# schematic.net
KiCad netlist of a schematic drawn in EAGLE
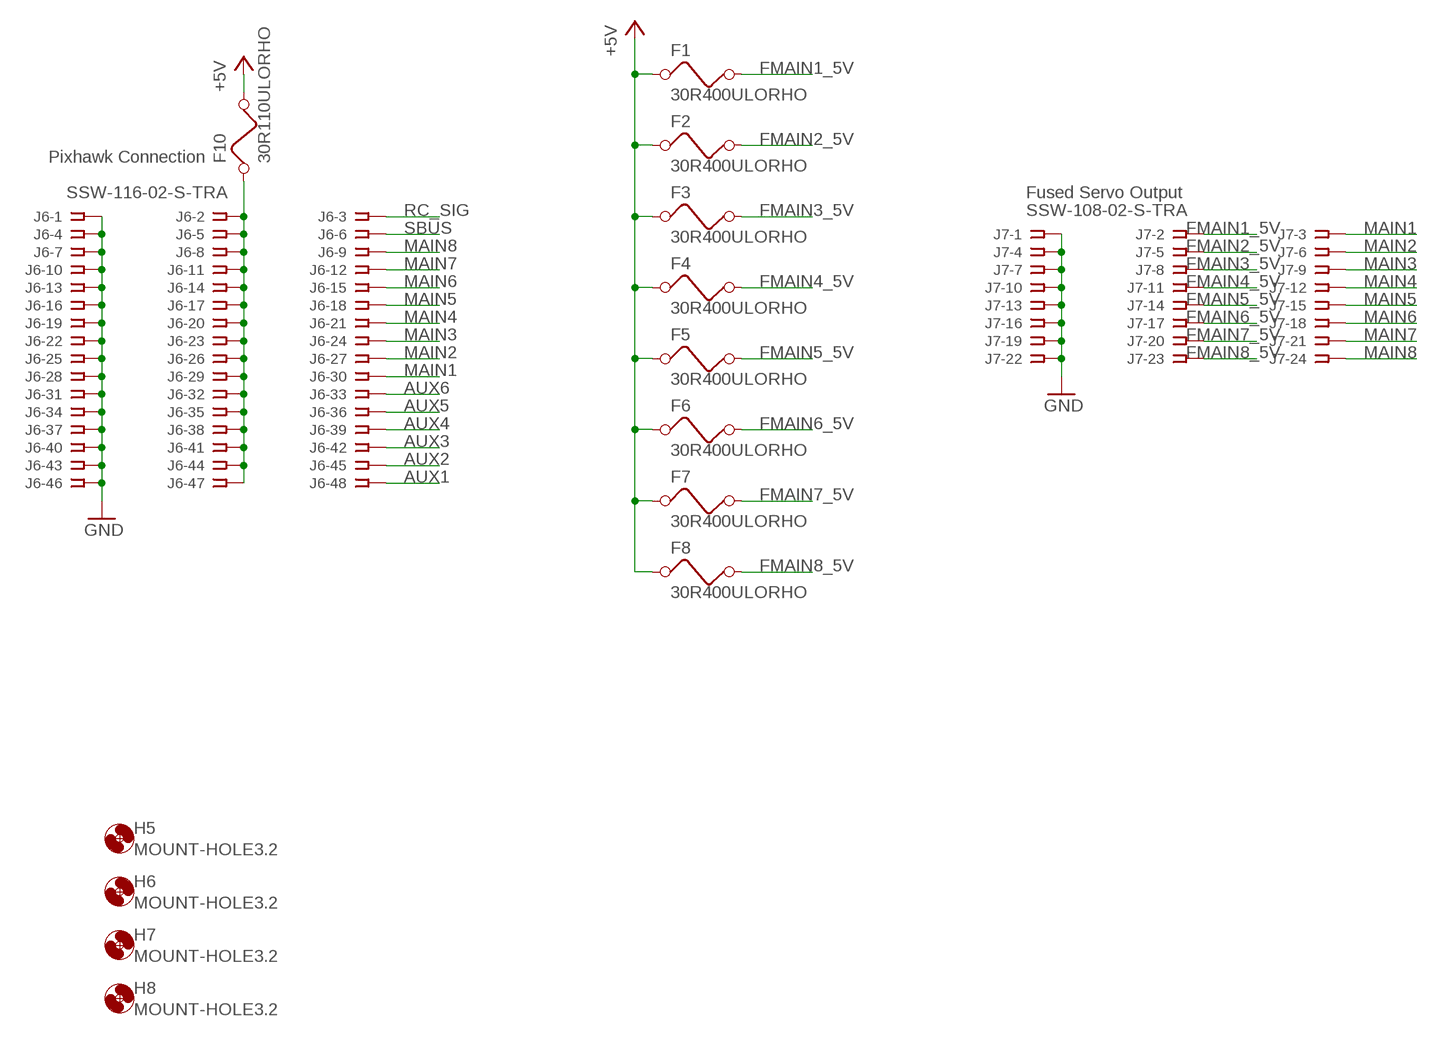
[diagram p0: schematic, sheet 1]
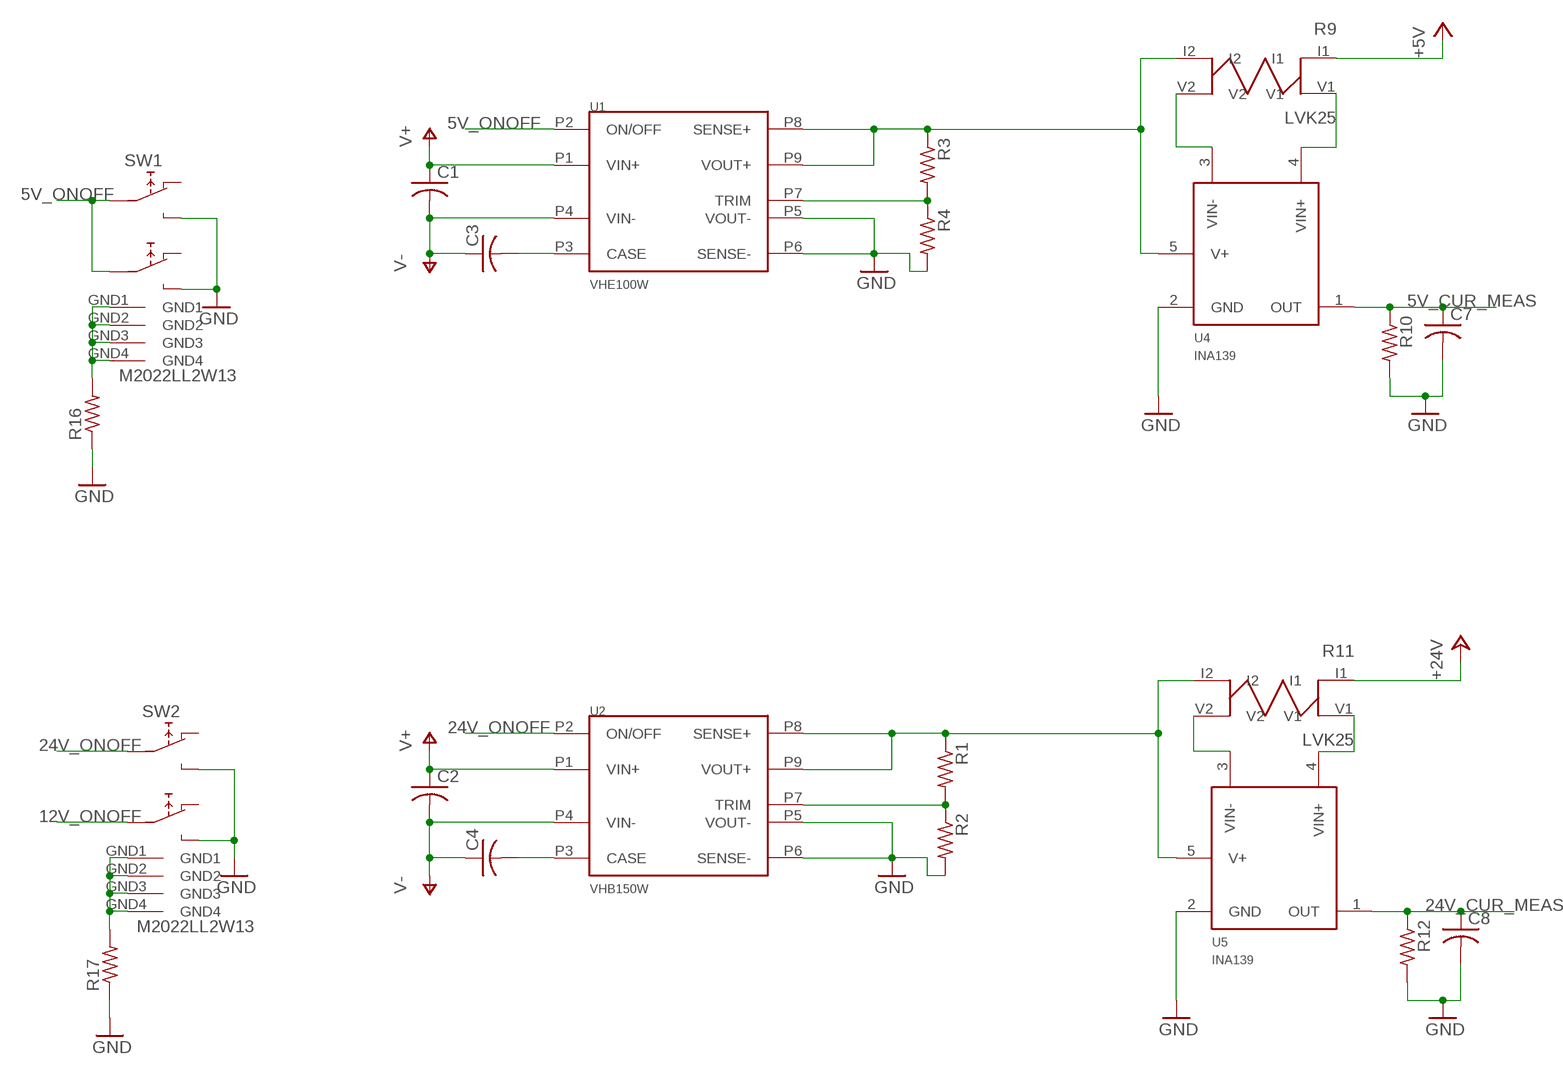
[diagram p1: schematic, sheet 2, part 1 of 2]
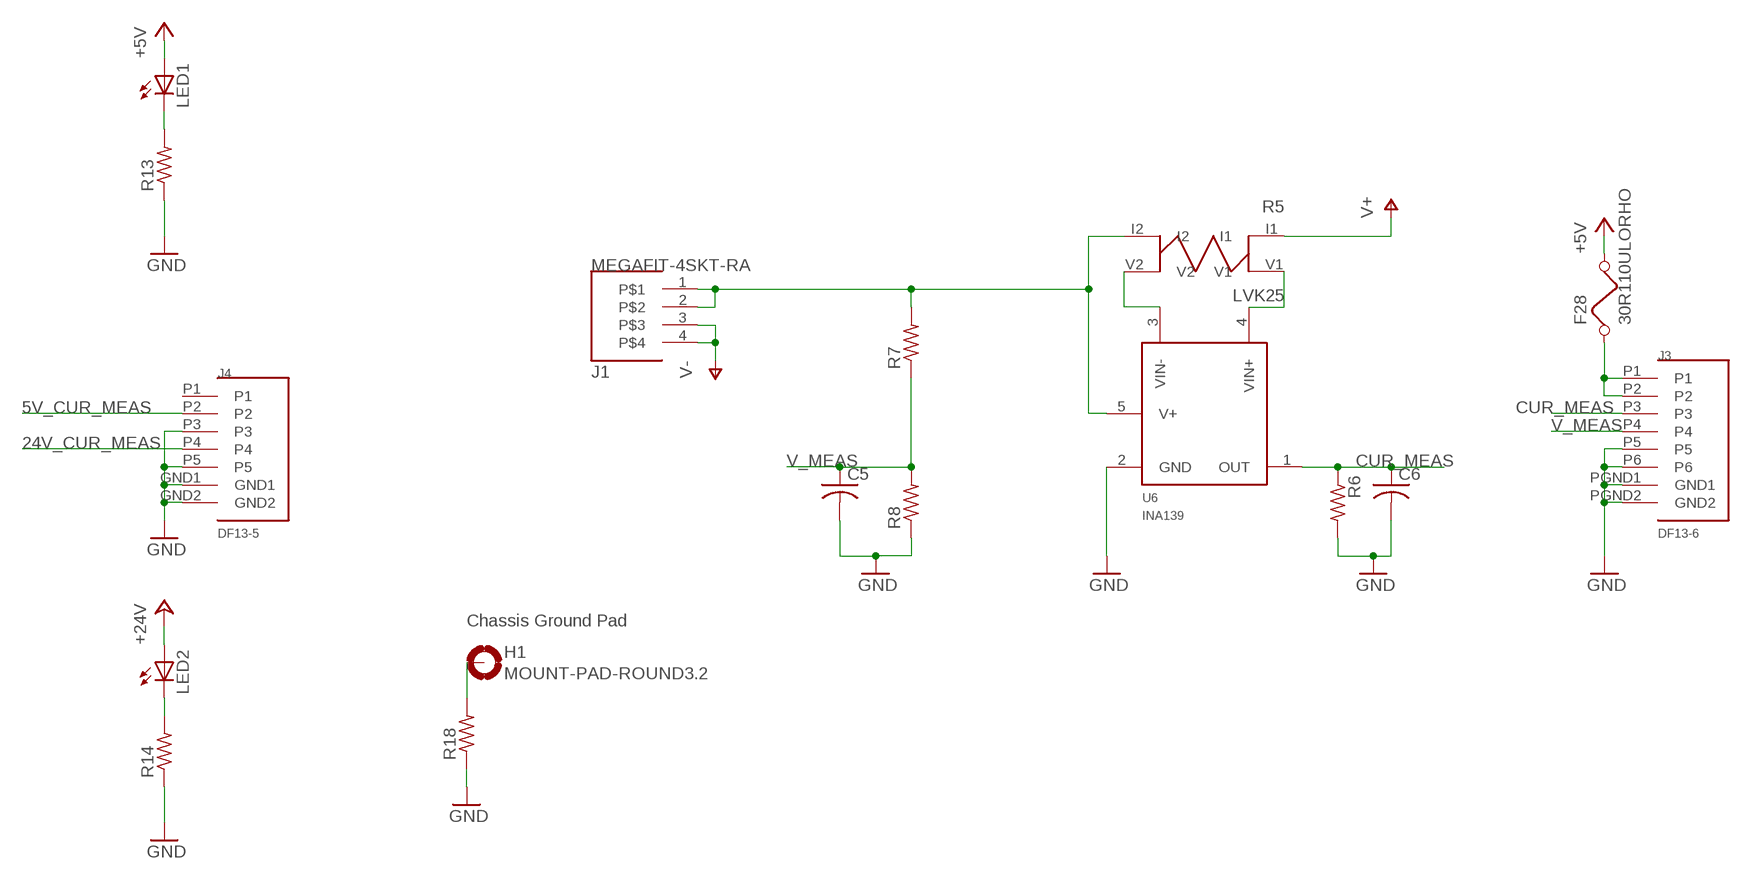
[diagram p2: schematic, sheet 2, part 2 of 2]
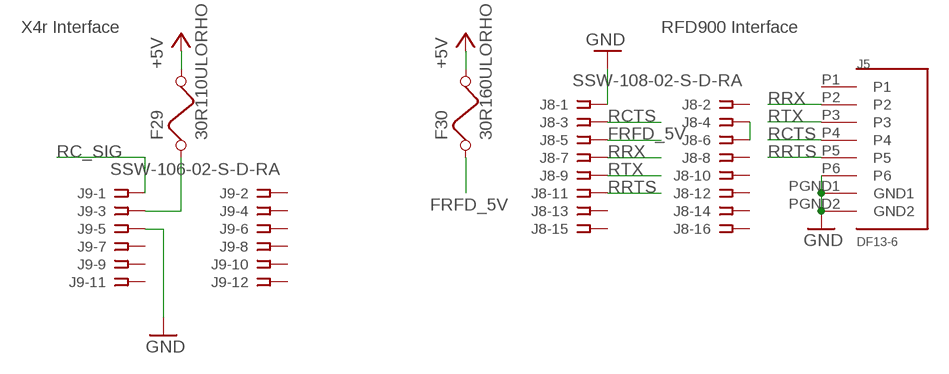
[diagram p3: schematic, sheet 3]
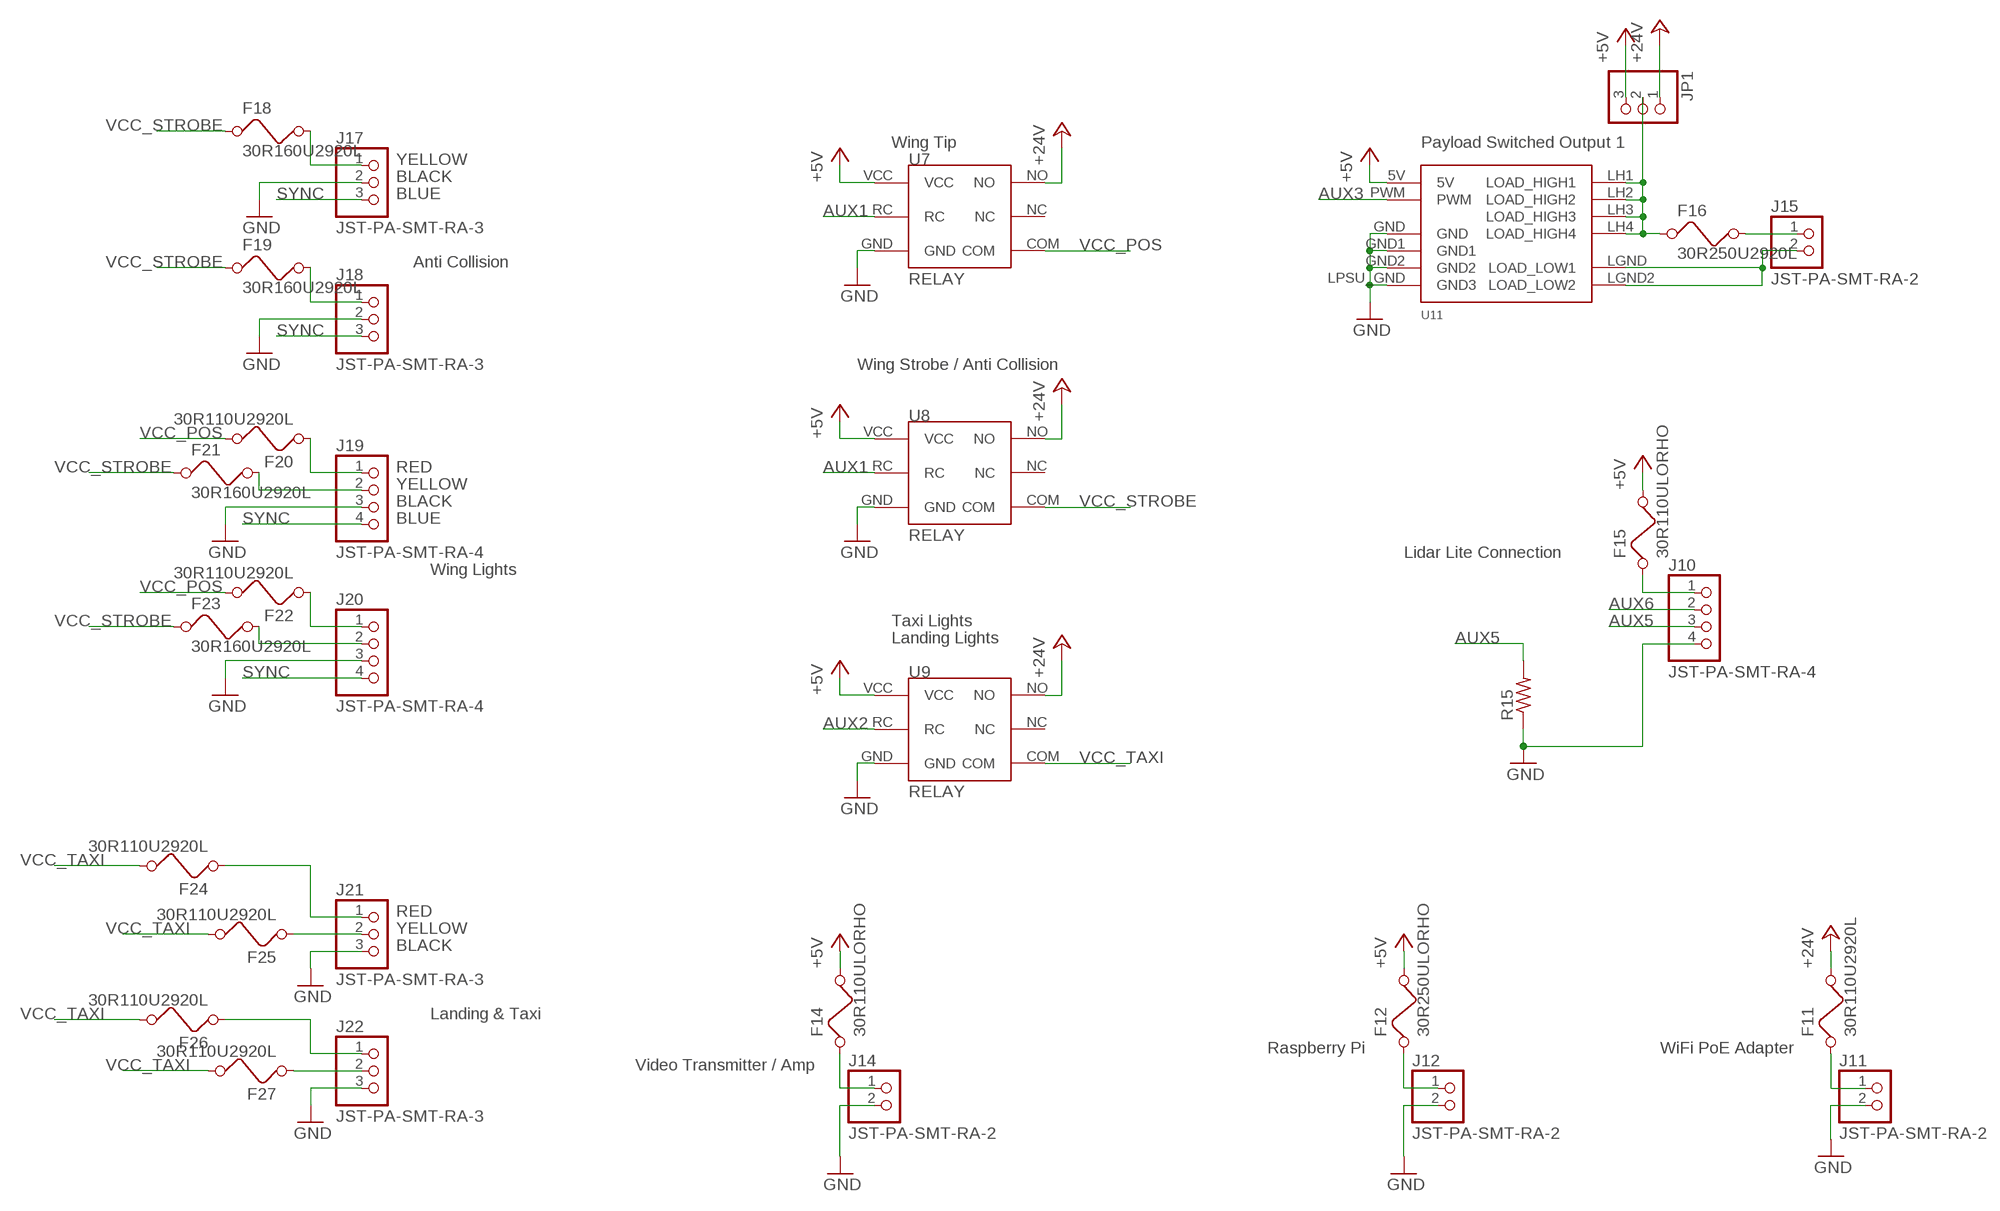
[diagram p4: schematic, sheet 4]

(export (version "E")
  (design (tool "Eeschema 10.0.6"))
  (components
    (comp (ref "F1")
      (value "30R400ULORHO")
      (footprint "eagle-import:1206")
      (libsource (lib "eagle-import") (part "30R400ULORHO"))
    )
    (comp (ref "F2")
      (value "30R400ULORHO")
      (footprint "eagle-import:1206")
      (libsource (lib "eagle-import") (part "30R400ULORHO"))
    )
    (comp (ref "F3")
      (value "30R400ULORHO")
      (footprint "eagle-import:1206")
      (libsource (lib "eagle-import") (part "30R400ULORHO"))
    )
    (comp (ref "F4")
      (value "30R400ULORHO")
      (footprint "eagle-import:1206")
      (libsource (lib "eagle-import") (part "30R400ULORHO"))
    )
    (comp (ref "F5")
      (value "30R400ULORHO")
      (footprint "eagle-import:1206")
      (libsource (lib "eagle-import") (part "30R400ULORHO"))
    )
    (comp (ref "F6")
      (value "30R400ULORHO")
      (footprint "eagle-import:1206")
      (libsource (lib "eagle-import") (part "30R400ULORHO"))
    )
    (comp (ref "F7")
      (value "30R400ULORHO")
      (footprint "eagle-import:1206")
      (libsource (lib "eagle-import") (part "30R400ULORHO"))
    )
    (comp (ref "F8")
      (value "30R400ULORHO")
      (footprint "eagle-import:1206")
      (libsource (lib "eagle-import") (part "30R400ULORHO"))
    )
    (comp (ref "F10")
      (value "30R110ULORHO")
      (footprint "eagle-import:1206")
      (libsource (lib "eagle-import") (part "30R110ULORHO"))
    )
    (comp (ref "H5")
      (value "MOUNT-HOLE3.2")
      (footprint "eagle-import:3,2")
      (libsource (lib "eagle-import") (part "MOUNT-HOLE3.2"))
    )
    (comp (ref "H6")
      (value "MOUNT-HOLE3.2")
      (footprint "eagle-import:3,2")
      (libsource (lib "eagle-import") (part "MOUNT-HOLE3.2"))
    )
    (comp (ref "H7")
      (value "MOUNT-HOLE3.2")
      (footprint "eagle-import:3,2")
      (libsource (lib "eagle-import") (part "MOUNT-HOLE3.2"))
    )
    (comp (ref "H8")
      (value "MOUNT-HOLE3.2")
      (footprint "eagle-import:3,2")
      (libsource (lib "eagle-import") (part "MOUNT-HOLE3.2"))
    )
    (comp (ref "J6")
      (value "SSW-116-02-S-TRA")
      (footprint "eagle-import:SSW-116-02-S-T-RA")
      (fields (field (name "MPN") "SSW-116-02-S-T-RA"))
      (libsource (lib "eagle-import") (part "SSW-116-02-S-TRA"))
    )
    (comp (ref "J7")
      (value "SSW-108-02-S-TRA")
      (footprint "eagle-import:SSW-108-02-S-T-RA")
      (fields (field (name "MPN") "SSW-108-02-S-T-RA"))
      (libsource (lib "eagle-import") (part "SSW-108-02-S-TRA"))
    )
    (comp (ref "C1")
      (value "C-USC1210")
      (footprint "eagle-import:C1210")
      (libsource (lib "eagle-import") (part "C-USC1210"))
    )
    (comp (ref "C2")
      (value "C-USC1210")
      (footprint "eagle-import:C1210")
      (libsource (lib "eagle-import") (part "C-USC1210"))
    )
    (comp (ref "C3")
      (value "C-USC1210")
      (footprint "eagle-import:C1210")
      (libsource (lib "eagle-import") (part "C-USC1210"))
    )
    (comp (ref "C4")
      (value "C-USC1210")
      (footprint "eagle-import:C1210")
      (libsource (lib "eagle-import") (part "C-USC1210"))
    )
    (comp (ref "C5")
      (value "C-USC0805")
      (footprint "eagle-import:C0805")
      (libsource (lib "eagle-import") (part "C-USC0805"))
    )
    (comp (ref "C6")
      (value "C-USC0805")
      (footprint "eagle-import:C0805")
      (libsource (lib "eagle-import") (part "C-USC0805"))
    )
    (comp (ref "C7")
      (value "C-USC0805")
      (footprint "eagle-import:C0805")
      (libsource (lib "eagle-import") (part "C-USC0805"))
    )
    (comp (ref "C8")
      (value "C-USC0805")
      (footprint "eagle-import:C0805")
      (libsource (lib "eagle-import") (part "C-USC0805"))
    )
    (comp (ref "F28")
      (value "30R110ULORHO")
      (footprint "eagle-import:1206")
      (libsource (lib "eagle-import") (part "30R110ULORHO"))
    )
    (comp (ref "H1")
      (value "MOUNT-PAD-ROUND3.2")
      (footprint "eagle-import:3,2-PAD")
      (libsource (lib "eagle-import") (part "MOUNT-PAD-ROUND3.2"))
    )
    (comp (ref "J1")
      (value "MEGAFIT-4SKT-RA")
      (footprint "eagle-import:MEGAFIT-4SKT-RA")
      (libsource (lib "eagle-import") (part "MEGAFIT-4SKT-RA"))
    )
    (comp (ref "J3")
      (value "DF13-6")
      (footprint "eagle-import:DF13-6")
      (libsource (lib "eagle-import") (part "DF13-6"))
    )
    (comp (ref "J4")
      (value "DF13-5")
      (footprint "eagle-import:DF13-5")
      (libsource (lib "eagle-import") (part "DF13-5"))
    )
    (comp (ref "LED1")
      (value "LEDCHIPLED_0805")
      (footprint "eagle-import:CHIPLED_0805")
      (libsource (lib "eagle-import") (part "LEDCHIPLED_0805"))
    )
    (comp (ref "LED2")
      (value "LEDCHIPLED_0805")
      (footprint "eagle-import:CHIPLED_0805")
      (libsource (lib "eagle-import") (part "LEDCHIPLED_0805"))
    )
    (comp (ref "R1")
      (value "R-US_M0805")
      (footprint "eagle-import:M0805")
      (libsource (lib "eagle-import") (part "R-US_M0805"))
    )
    (comp (ref "R2")
      (value "R-US_M0805")
      (footprint "eagle-import:M0805")
      (libsource (lib "eagle-import") (part "R-US_M0805"))
    )
    (comp (ref "R3")
      (value "R-US_M0805")
      (footprint "eagle-import:M0805")
      (libsource (lib "eagle-import") (part "R-US_M0805"))
    )
    (comp (ref "R4")
      (value "R-US_M0805")
      (footprint "eagle-import:M0805")
      (libsource (lib "eagle-import") (part "R-US_M0805"))
    )
    (comp (ref "R5")
      (value "LVK25")
      (footprint "eagle-import:LVK25")
      (libsource (lib "eagle-import") (part "LVK25"))
    )
    (comp (ref "R6")
      (value "R-US_M0805")
      (footprint "eagle-import:M0805")
      (libsource (lib "eagle-import") (part "R-US_M0805"))
    )
    (comp (ref "R7")
      (value "R-US_M0805")
      (footprint "eagle-import:M0805")
      (libsource (lib "eagle-import") (part "R-US_M0805"))
    )
    (comp (ref "R8")
      (value "R-US_M0805")
      (footprint "eagle-import:M0805")
      (libsource (lib "eagle-import") (part "R-US_M0805"))
    )
    (comp (ref "R9")
      (value "LVK25")
      (footprint "eagle-import:LVK25")
      (libsource (lib "eagle-import") (part "LVK25"))
    )
    (comp (ref "R10")
      (value "R-US_M0805")
      (footprint "eagle-import:M0805")
      (libsource (lib "eagle-import") (part "R-US_M0805"))
    )
    (comp (ref "R11")
      (value "LVK25")
      (footprint "eagle-import:LVK25")
      (libsource (lib "eagle-import") (part "LVK25"))
    )
    (comp (ref "R12")
      (value "R-US_M0805")
      (footprint "eagle-import:M0805")
      (libsource (lib "eagle-import") (part "R-US_M0805"))
    )
    (comp (ref "R13")
      (value "R-US_M0805")
      (footprint "eagle-import:M0805")
      (libsource (lib "eagle-import") (part "R-US_M0805"))
    )
    (comp (ref "R14")
      (value "R-US_M0805")
      (footprint "eagle-import:M0805")
      (libsource (lib "eagle-import") (part "R-US_M0805"))
    )
    (comp (ref "R16")
      (value "R-US_M0805")
      (footprint "eagle-import:M0805")
      (libsource (lib "eagle-import") (part "R-US_M0805"))
    )
    (comp (ref "R17")
      (value "R-US_M0805")
      (footprint "eagle-import:M0805")
      (libsource (lib "eagle-import") (part "R-US_M0805"))
    )
    (comp (ref "R18")
      (value "R-US_M0805")
      (footprint "eagle-import:M0805")
      (libsource (lib "eagle-import") (part "R-US_M0805"))
    )
    (comp (ref "SW1")
      (value "M2022LL2W13")
      (footprint "eagle-import:M2022LL2W13")
      (libsource (lib "eagle-import") (part "M2022LL2W13"))
    )
    (comp (ref "SW2")
      (value "M2022LL2W13")
      (footprint "eagle-import:M2022LL2W13")
      (libsource (lib "eagle-import") (part "M2022LL2W13"))
    )
    (comp (ref "U1")
      (value "VHE100W")
      (footprint "eagle-import:VHE100W")
      (libsource (lib "eagle-import") (part "VHE100W"))
    )
    (comp (ref "U2")
      (value "VHB150W")
      (footprint "eagle-import:VHB150W")
      (libsource (lib "eagle-import") (part "VHB150W"))
    )
    (comp (ref "U4")
      (value "INA139")
      (footprint "eagle-import:SOT23-5")
      (libsource (lib "eagle-import") (part "INA139"))
    )
    (comp (ref "U5")
      (value "INA139")
      (footprint "eagle-import:SOT23-5")
      (libsource (lib "eagle-import") (part "INA139"))
    )
    (comp (ref "U6")
      (value "INA139")
      (footprint "eagle-import:SOT23-5")
      (libsource (lib "eagle-import") (part "INA139"))
    )
    (comp (ref "F11")
      (value "30R110U2920L")
      (footprint "eagle-import:2920L")
      (libsource (lib "eagle-import") (part "30R110U2920L"))
    )
    (comp (ref "F12")
      (value "30R250ULORHO")
      (footprint "eagle-import:1206")
      (libsource (lib "eagle-import") (part "30R250ULORHO"))
    )
    (comp (ref "F14")
      (value "30R110ULORHO")
      (footprint "eagle-import:1206")
      (libsource (lib "eagle-import") (part "30R110ULORHO"))
    )
    (comp (ref "F15")
      (value "30R110ULORHO")
      (footprint "eagle-import:1206")
      (libsource (lib "eagle-import") (part "30R110ULORHO"))
    )
    (comp (ref "F16")
      (value "30R250U2920L")
      (footprint "eagle-import:2920L")
      (libsource (lib "eagle-import") (part "30R250U2920L"))
    )
    (comp (ref "F18")
      (value "30R160U2920L")
      (footprint "eagle-import:2920L")
      (libsource (lib "eagle-import") (part "30R160U2920L"))
    )
    (comp (ref "F19")
      (value "30R160U2920L")
      (footprint "eagle-import:2920L")
      (libsource (lib "eagle-import") (part "30R160U2920L"))
    )
    (comp (ref "F20")
      (value "30R110U2920L")
      (footprint "eagle-import:2920L")
      (libsource (lib "eagle-import") (part "30R110U2920L"))
    )
    (comp (ref "F21")
      (value "30R160U2920L")
      (footprint "eagle-import:2920L")
      (libsource (lib "eagle-import") (part "30R160U2920L"))
    )
    (comp (ref "F22")
      (value "30R110U2920L")
      (footprint "eagle-import:2920L")
      (libsource (lib "eagle-import") (part "30R110U2920L"))
    )
    (comp (ref "F23")
      (value "30R160U2920L")
      (footprint "eagle-import:2920L")
      (libsource (lib "eagle-import") (part "30R160U2920L"))
    )
    (comp (ref "F24")
      (value "30R110U2920L")
      (footprint "eagle-import:2920L")
      (libsource (lib "eagle-import") (part "30R110U2920L"))
    )
    (comp (ref "F25")
      (value "30R110U2920L")
      (footprint "eagle-import:2920L")
      (libsource (lib "eagle-import") (part "30R110U2920L"))
    )
    (comp (ref "F26")
      (value "30R110U2920L")
      (footprint "eagle-import:2920L")
      (libsource (lib "eagle-import") (part "30R110U2920L"))
    )
    (comp (ref "F27")
      (value "30R110U2920L")
      (footprint "eagle-import:2920L")
      (libsource (lib "eagle-import") (part "30R110U2920L"))
    )
    (comp (ref "J10")
      (value "JST-PA-SMT-RA-4")
      (footprint "eagle-import:JST-PA-SMT-RA-4")
      (libsource (lib "eagle-import") (part "JST-PA-SMT-RA-4"))
    )
    (comp (ref "J11")
      (value "JST-PA-SMT-RA-2")
      (footprint "eagle-import:JST-PA-SMT-RA-2")
      (libsource (lib "eagle-import") (part "JST-PA-SMT-RA-2"))
    )
    (comp (ref "J12")
      (value "JST-PA-SMT-RA-2")
      (footprint "eagle-import:JST-PA-SMT-RA-2")
      (libsource (lib "eagle-import") (part "JST-PA-SMT-RA-2"))
    )
    (comp (ref "J14")
      (value "JST-PA-SMT-RA-2")
      (footprint "eagle-import:JST-PA-SMT-RA-2")
      (libsource (lib "eagle-import") (part "JST-PA-SMT-RA-2"))
    )
    (comp (ref "J15")
      (value "JST-PA-SMT-RA-2")
      (footprint "eagle-import:JST-PA-SMT-RA-2")
      (libsource (lib "eagle-import") (part "JST-PA-SMT-RA-2"))
    )
    (comp (ref "J17")
      (value "JST-PA-SMT-RA-3")
      (footprint "eagle-import:JST-PA-SMT-RA-3")
      (libsource (lib "eagle-import") (part "JST-PA-SMT-RA-3"))
    )
    (comp (ref "J18")
      (value "JST-PA-SMT-RA-3")
      (footprint "eagle-import:JST-PA-SMT-RA-3")
      (libsource (lib "eagle-import") (part "JST-PA-SMT-RA-3"))
    )
    (comp (ref "J19")
      (value "JST-PA-SMT-RA-4")
      (footprint "eagle-import:JST-PA-SMT-RA-4")
      (libsource (lib "eagle-import") (part "JST-PA-SMT-RA-4"))
    )
    (comp (ref "J20")
      (value "JST-PA-SMT-RA-4")
      (footprint "eagle-import:JST-PA-SMT-RA-4")
      (libsource (lib "eagle-import") (part "JST-PA-SMT-RA-4"))
    )
    (comp (ref "J21")
      (value "JST-PA-SMT-RA-3")
      (footprint "eagle-import:JST-PA-SMT-RA-3")
      (libsource (lib "eagle-import") (part "JST-PA-SMT-RA-3"))
    )
    (comp (ref "J22")
      (value "JST-PA-SMT-RA-3")
      (footprint "eagle-import:JST-PA-SMT-RA-3")
      (libsource (lib "eagle-import") (part "JST-PA-SMT-RA-3"))
    )
    (comp (ref "JP1")
      (value "PINHD-1X3")
      (footprint "eagle-import:1X03")
      (libsource (lib "eagle-import") (part "PINHD-1X3"))
    )
    (comp (ref "R15")
      (value "R-US_M0805")
      (footprint "eagle-import:M0805")
      (libsource (lib "eagle-import") (part "R-US_M0805"))
    )
    (comp (ref "U7")
      (value "RELAY")
      (footprint "eagle-import:RELAY")
      (libsource (lib "eagle-import") (part "RELAY"))
    )
    (comp (ref "U8")
      (value "RELAY")
      (footprint "eagle-import:RELAY")
      (libsource (lib "eagle-import") (part "RELAY"))
    )
    (comp (ref "U9")
      (value "RELAY")
      (footprint "eagle-import:RELAY")
      (libsource (lib "eagle-import") (part "RELAY"))
    )
    (comp (ref "U11")
      (value "MED_MOSFET")
      (footprint "eagle-import:MED_MOSFET")
      (libsource (lib "eagle-import") (part "MED_MOSFET"))
    )
    (comp (ref "F29")
      (value "30R110ULORHO")
      (footprint "eagle-import:1206")
      (libsource (lib "eagle-import") (part "30R110ULORHO"))
    )
    (comp (ref "F30")
      (value "30R160ULORHO")
      (footprint "eagle-import:1206")
      (libsource (lib "eagle-import") (part "30R160ULORHO"))
    )
    (comp (ref "J5")
      (value "DF13-6")
      (footprint "eagle-import:DF13-6")
      (libsource (lib "eagle-import") (part "DF13-6"))
    )
    (comp (ref "J8")
      (value "SSW-108-02-S-D-RA")
      (footprint "eagle-import:TSW-108-02-S-D-RA")
      (libsource (lib "eagle-import") (part "SSW-108-02-S-D-RA"))
    )
    (comp (ref "J9")
      (value "SSW-106-02-S-D-RA")
      (footprint "eagle-import:TSW-106-02-S-D-RA")
      (libsource (lib "eagle-import") (part "SSW-106-02-S-D-RA"))
    )
  )
  (nets
    (net (code "1") (name "+5V") (class "Default")
      (node (ref "F1") (pin "1") (pinfunction "1_1") (pintype "passive"))
      (node (ref "F10") (pin "2") (pinfunction "2_2") (pintype "passive"))
      (node (ref "F12") (pin "2") (pinfunction "2_2") (pintype "passive"))
      (node (ref "F14") (pin "2") (pinfunction "2_2") (pintype "passive"))
      (node (ref "F15") (pin "2") (pinfunction "2_2") (pintype "passive"))
      (node (ref "F2") (pin "1") (pinfunction "1_1") (pintype "passive"))
      (node (ref "F28") (pin "2") (pinfunction "2_2") (pintype "passive"))
      (node (ref "F29") (pin "2") (pinfunction "2_2") (pintype "passive"))
      (node (ref "F3") (pin "1") (pinfunction "1_1") (pintype "passive"))
      (node (ref "F30") (pin "2") (pinfunction "2_2") (pintype "passive"))
      (node (ref "F4") (pin "1") (pinfunction "1_1") (pintype "passive"))
      (node (ref "F5") (pin "1") (pinfunction "1_1") (pintype "passive"))
      (node (ref "F6") (pin "1") (pinfunction "1_1") (pintype "passive"))
      (node (ref "F7") (pin "1") (pinfunction "1_1") (pintype "passive"))
      (node (ref "F8") (pin "1") (pinfunction "1_1") (pintype "passive"))
      (node (ref "JP1") (pin "3") (pinfunction "3_3") (pintype "passive"))
      (node (ref "LED1") (pin "A") (pinfunction "A_A") (pintype "passive"))
      (node (ref "R9") (pin "I1") (pinfunction "I1_I1") (pintype "bidirectional"))
      (node (ref "U11") (pin "5V") (pinfunction "5V_5V") (pintype "bidirectional"))
      (node (ref "U7") (pin "VCC") (pinfunction "VCC_VCC") (pintype "bidirectional"))
      (node (ref "U8") (pin "VCC") (pinfunction "VCC_VCC") (pintype "bidirectional"))
      (node (ref "U9") (pin "VCC") (pinfunction "VCC_VCC") (pintype "bidirectional"))
    )
    (net (code "2") (name "+24V") (class "Default")
      (node (ref "F11") (pin "P$2") (pinfunction "2_P$2") (pintype "passive"))
      (node (ref "JP1") (pin "1") (pinfunction "1_1") (pintype "passive"))
      (node (ref "LED2") (pin "A") (pinfunction "A_A") (pintype "passive"))
      (node (ref "R11") (pin "I1") (pinfunction "I1_I1") (pintype "bidirectional"))
      (node (ref "U7") (pin "NO") (pinfunction "NO_NO") (pintype "bidirectional"))
      (node (ref "U8") (pin "NO") (pinfunction "NO_NO") (pintype "bidirectional"))
      (node (ref "U9") (pin "NO") (pinfunction "NO_NO") (pintype "bidirectional"))
    )
    (net (code "3") (name "5V_CUR_MEAS") (class "Default")
      (node (ref "C7") (pin "1") (pinfunction "1_1") (pintype "passive"))
      (node (ref "J4") (pin "P2") (pinfunction "P2_P2") (pintype "bidirectional"))
      (node (ref "R10") (pin "1") (pinfunction "1_1") (pintype "passive"))
      (node (ref "U4") (pin "1") (pinfunction "OUT_1") (pintype "bidirectional"))
    )
    (net (code "4") (name "5V_ONOFF") (class "Default")
      (node (ref "SW1") (pin "P2") (pinfunction "1A_P2") (pintype "passive"))
      (node (ref "SW1") (pin "P5") (pinfunction "1A1_P5") (pintype "passive"))
      (node (ref "U1") (pin "P2") (pinfunction "ON/OFF_P2") (pintype "bidirectional"))
    )
    (net (code "5") (name "12V_ONOFF") (class "Default")
      (node (ref "SW2") (pin "P5") (pinfunction "1A1_P5") (pintype "passive"))
    )
    (net (code "6") (name "24V_CUR_MEAS") (class "Default")
      (node (ref "C8") (pin "1") (pinfunction "1_1") (pintype "passive"))
      (node (ref "J4") (pin "P4") (pinfunction "P4_P4") (pintype "bidirectional"))
      (node (ref "R12") (pin "1") (pinfunction "1_1") (pintype "passive"))
      (node (ref "U5") (pin "1") (pinfunction "OUT_1") (pintype "bidirectional"))
    )
    (net (code "7") (name "24V_ONOFF") (class "Default")
      (node (ref "SW2") (pin "P2") (pinfunction "1A_P2") (pintype "passive"))
      (node (ref "U2") (pin "P2") (pinfunction "ON/OFF_P2") (pintype "bidirectional"))
    )
    (net (code "8") (name "AUX1") (class "Default")
      (node (ref "J6") (pin "48") (pinfunction "1_48") (pintype "passive"))
      (node (ref "U7") (pin "RC") (pinfunction "RC_RC") (pintype "bidirectional"))
      (node (ref "U8") (pin "RC") (pinfunction "RC_RC") (pintype "bidirectional"))
    )
    (net (code "9") (name "AUX2") (class "Default")
      (node (ref "J6") (pin "45") (pinfunction "1_45") (pintype "passive"))
      (node (ref "U9") (pin "RC") (pinfunction "RC_RC") (pintype "bidirectional"))
    )
    (net (code "10") (name "AUX3") (class "Default")
      (node (ref "J6") (pin "42") (pinfunction "1_42") (pintype "passive"))
      (node (ref "U11") (pin "PWM") (pinfunction "PWM_PWM") (pintype "bidirectional"))
    )
    (net (code "11") (name "AUX4") (class "Default")
      (node (ref "J6") (pin "39") (pinfunction "1_39") (pintype "passive"))
    )
    (net (code "12") (name "AUX5") (class "Default")
      (node (ref "J10") (pin "3") (pinfunction "3_3") (pintype "passive"))
      (node (ref "J6") (pin "36") (pinfunction "1_36") (pintype "passive"))
      (node (ref "R15") (pin "2") (pinfunction "2_2") (pintype "passive"))
    )
    (net (code "13") (name "AUX6") (class "Default")
      (node (ref "J10") (pin "2") (pinfunction "2_2") (pintype "passive"))
      (node (ref "J6") (pin "33") (pinfunction "1_33") (pintype "passive"))
    )
    (net (code "14") (name "CUR_MEAS") (class "Default")
      (node (ref "C6") (pin "1") (pinfunction "1_1") (pintype "passive"))
      (node (ref "J3") (pin "P3") (pinfunction "P3_P3") (pintype "bidirectional"))
      (node (ref "R6") (pin "1") (pinfunction "1_1") (pintype "passive"))
      (node (ref "U6") (pin "1") (pinfunction "OUT_1") (pintype "bidirectional"))
    )
    (net (code "15") (name "FMAIN1_5V") (class "Default")
      (node (ref "F1") (pin "2") (pinfunction "2_2") (pintype "passive"))
      (node (ref "J7") (pin "2") (pinfunction "1_2") (pintype "passive"))
    )
    (net (code "16") (name "FMAIN2_5V") (class "Default")
      (node (ref "F2") (pin "2") (pinfunction "2_2") (pintype "passive"))
      (node (ref "J7") (pin "5") (pinfunction "1_5") (pintype "passive"))
    )
    (net (code "17") (name "FMAIN3_5V") (class "Default")
      (node (ref "F3") (pin "2") (pinfunction "2_2") (pintype "passive"))
      (node (ref "J7") (pin "8") (pinfunction "1_8") (pintype "passive"))
    )
    (net (code "18") (name "FMAIN4_5V") (class "Default")
      (node (ref "F4") (pin "2") (pinfunction "2_2") (pintype "passive"))
      (node (ref "J7") (pin "11") (pinfunction "1_11") (pintype "passive"))
    )
    (net (code "19") (name "FMAIN5_5V") (class "Default")
      (node (ref "F5") (pin "2") (pinfunction "2_2") (pintype "passive"))
      (node (ref "J7") (pin "14") (pinfunction "1_14") (pintype "passive"))
    )
    (net (code "20") (name "FMAIN6_5V") (class "Default")
      (node (ref "F6") (pin "2") (pinfunction "2_2") (pintype "passive"))
      (node (ref "J7") (pin "17") (pinfunction "1_17") (pintype "passive"))
    )
    (net (code "21") (name "FMAIN7_5V") (class "Default")
      (node (ref "F7") (pin "2") (pinfunction "2_2") (pintype "passive"))
      (node (ref "J7") (pin "20") (pinfunction "1_20") (pintype "passive"))
    )
    (net (code "22") (name "FMAIN8_5V") (class "Default")
      (node (ref "F8") (pin "2") (pinfunction "2_2") (pintype "passive"))
      (node (ref "J7") (pin "23") (pinfunction "1_23") (pintype "passive"))
    )
    (net (code "23") (name "FRFD_5V") (class "Default")
      (node (ref "F30") (pin "1") (pinfunction "1_1") (pintype "passive"))
      (node (ref "J8") (pin "5") (pinfunction "1_5") (pintype "passive"))
    )
    (net (code "24") (name "GND") (class "Default")
      (node (ref "C5") (pin "2") (pinfunction "2_2") (pintype "passive"))
      (node (ref "C6") (pin "2") (pinfunction "2_2") (pintype "passive"))
      (node (ref "C7") (pin "2") (pinfunction "2_2") (pintype "passive"))
      (node (ref "C8") (pin "2") (pinfunction "2_2") (pintype "passive"))
      (node (ref "J10") (pin "4") (pinfunction "4_4") (pintype "passive"))
      (node (ref "J11") (pin "2") (pinfunction "2_2") (pintype "passive"))
      (node (ref "J12") (pin "2") (pinfunction "2_2") (pintype "passive"))
      (node (ref "J14") (pin "2") (pinfunction "2_2") (pintype "passive"))
      (node (ref "J17") (pin "2") (pinfunction "2_2") (pintype "passive"))
      (node (ref "J18") (pin "2") (pinfunction "2_2") (pintype "passive"))
      (node (ref "J19") (pin "3") (pinfunction "3_3") (pintype "passive"))
      (node (ref "J20") (pin "3") (pinfunction "3_3") (pintype "passive"))
      (node (ref "J21") (pin "3") (pinfunction "3_3") (pintype "passive"))
      (node (ref "J22") (pin "3") (pinfunction "3_3") (pintype "passive"))
      (node (ref "J3") (pin "P5") (pinfunction "P5_P5") (pintype "bidirectional"))
      (node (ref "J3") (pin "P6") (pinfunction "P6_P6") (pintype "bidirectional"))
      (node (ref "J3") (pin "PGND1") (pinfunction "GND1_PGND1") (pintype "power_in"))
      (node (ref "J3") (pin "PGND2") (pinfunction "GND2_PGND2") (pintype "power_in"))
      (node (ref "J4") (pin "GND1") (pinfunction "GND1_GND1") (pintype "power_in"))
      (node (ref "J4") (pin "GND2") (pinfunction "GND2_GND2") (pintype "power_in"))
      (node (ref "J4") (pin "P3") (pinfunction "P3_P3") (pintype "bidirectional"))
      (node (ref "J4") (pin "P5") (pinfunction "P5_P5") (pintype "bidirectional"))
      (node (ref "J5") (pin "P6") (pinfunction "P6_P6") (pintype "bidirectional"))
      (node (ref "J5") (pin "PGND1") (pinfunction "GND1_PGND1") (pintype "power_in"))
      (node (ref "J5") (pin "PGND2") (pinfunction "GND2_PGND2") (pintype "power_in"))
      (node (ref "J6") (pin "1") (pinfunction "1_1") (pintype "passive"))
      (node (ref "J6") (pin "10") (pinfunction "1_10") (pintype "passive"))
      (node (ref "J6") (pin "13") (pinfunction "1_13") (pintype "passive"))
      (node (ref "J6") (pin "16") (pinfunction "1_16") (pintype "passive"))
      (node (ref "J6") (pin "19") (pinfunction "1_19") (pintype "passive"))
      (node (ref "J6") (pin "22") (pinfunction "1_22") (pintype "passive"))
      (node (ref "J6") (pin "25") (pinfunction "1_25") (pintype "passive"))
      (node (ref "J6") (pin "28") (pinfunction "1_28") (pintype "passive"))
      (node (ref "J6") (pin "31") (pinfunction "1_31") (pintype "passive"))
      (node (ref "J6") (pin "34") (pinfunction "1_34") (pintype "passive"))
      (node (ref "J6") (pin "37") (pinfunction "1_37") (pintype "passive"))
      (node (ref "J6") (pin "4") (pinfunction "1_4") (pintype "passive"))
      (node (ref "J6") (pin "40") (pinfunction "1_40") (pintype "passive"))
      (node (ref "J6") (pin "43") (pinfunction "1_43") (pintype "passive"))
      (node (ref "J6") (pin "46") (pinfunction "1_46") (pintype "passive"))
      (node (ref "J6") (pin "7") (pinfunction "1_7") (pintype "passive"))
      (node (ref "J7") (pin "1") (pinfunction "1_1") (pintype "passive"))
      (node (ref "J7") (pin "10") (pinfunction "1_10") (pintype "passive"))
      (node (ref "J7") (pin "13") (pinfunction "1_13") (pintype "passive"))
      (node (ref "J7") (pin "16") (pinfunction "1_16") (pintype "passive"))
      (node (ref "J7") (pin "19") (pinfunction "1_19") (pintype "passive"))
      (node (ref "J7") (pin "22") (pinfunction "1_22") (pintype "passive"))
      (node (ref "J7") (pin "4") (pinfunction "1_4") (pintype "passive"))
      (node (ref "J7") (pin "7") (pinfunction "1_7") (pintype "passive"))
      (node (ref "J8") (pin "1") (pinfunction "1_1") (pintype "passive"))
      (node (ref "J9") (pin "5") (pinfunction "1_5") (pintype "passive"))
      (node (ref "R10") (pin "2") (pinfunction "2_2") (pintype "passive"))
      (node (ref "R12") (pin "2") (pinfunction "2_2") (pintype "passive"))
      (node (ref "R13") (pin "1") (pinfunction "1_1") (pintype "passive"))
      (node (ref "R14") (pin "1") (pinfunction "1_1") (pintype "passive"))
      (node (ref "R15") (pin "1") (pinfunction "1_1") (pintype "passive"))
      (node (ref "R16") (pin "1") (pinfunction "1_1") (pintype "passive"))
      (node (ref "R17") (pin "1") (pinfunction "1_1") (pintype "passive"))
      (node (ref "R18") (pin "1") (pinfunction "1_1") (pintype "passive"))
      (node (ref "R2") (pin "2") (pinfunction "2_2") (pintype "passive"))
      (node (ref "R4") (pin "2") (pinfunction "2_2") (pintype "passive"))
      (node (ref "R6") (pin "2") (pinfunction "2_2") (pintype "passive"))
      (node (ref "R8") (pin "1") (pinfunction "1_1") (pintype "passive"))
      (node (ref "SW1") (pin "P1") (pinfunction "NO_P1") (pintype "passive"))
      (node (ref "SW1") (pin "P4") (pinfunction "NO1_P4") (pintype "passive"))
      (node (ref "SW2") (pin "P1") (pinfunction "NO_P1") (pintype "passive"))
      (node (ref "SW2") (pin "P4") (pinfunction "NO1_P4") (pintype "passive"))
      (node (ref "U1") (pin "P5") (pinfunction "VOUT-_P5") (pintype "bidirectional"))
      (node (ref "U1") (pin "P6") (pinfunction "SENSE-_P6") (pintype "bidirectional"))
      (node (ref "U11") (pin "GND") (pinfunction "GND_GND") (pintype "bidirectional"))
      (node (ref "U11") (pin "GND1") (pinfunction "GND1_GND1") (pintype "bidirectional"))
      (node (ref "U11") (pin "GND2") (pinfunction "GND2_GND2") (pintype "bidirectional"))
      (node (ref "U11") (pin "LPSU_GND") (pinfunction "GND3_LPSU_GND") (pintype "bidirectional"))
      (node (ref "U2") (pin "P5") (pinfunction "VOUT-_P5") (pintype "bidirectional"))
      (node (ref "U2") (pin "P6") (pinfunction "SENSE-_P6") (pintype "bidirectional"))
      (node (ref "U4") (pin "2") (pinfunction "GND_2") (pintype "bidirectional"))
      (node (ref "U5") (pin "2") (pinfunction "GND_2") (pintype "bidirectional"))
      (node (ref "U6") (pin "2") (pinfunction "GND_2") (pintype "bidirectional"))
      (node (ref "U7") (pin "GND") (pinfunction "GND_GND") (pintype "bidirectional"))
      (node (ref "U8") (pin "GND") (pinfunction "GND_GND") (pintype "bidirectional"))
      (node (ref "U9") (pin "GND") (pinfunction "GND_GND") (pintype "bidirectional"))
    )
    (net (code "25") (name "MAIN1") (class "Default")
      (node (ref "J6") (pin "30") (pinfunction "1_30") (pintype "passive"))
      (node (ref "J7") (pin "3") (pinfunction "1_3") (pintype "passive"))
    )
    (net (code "26") (name "MAIN2") (class "Default")
      (node (ref "J6") (pin "27") (pinfunction "1_27") (pintype "passive"))
      (node (ref "J7") (pin "6") (pinfunction "1_6") (pintype "passive"))
    )
    (net (code "27") (name "MAIN3") (class "Default")
      (node (ref "J6") (pin "24") (pinfunction "1_24") (pintype "passive"))
      (node (ref "J7") (pin "9") (pinfunction "1_9") (pintype "passive"))
    )
    (net (code "28") (name "MAIN4") (class "Default")
      (node (ref "J6") (pin "21") (pinfunction "1_21") (pintype "passive"))
      (node (ref "J7") (pin "12") (pinfunction "1_12") (pintype "passive"))
    )
    (net (code "29") (name "MAIN5") (class "Default")
      (node (ref "J6") (pin "18") (pinfunction "1_18") (pintype "passive"))
      (node (ref "J7") (pin "15") (pinfunction "1_15") (pintype "passive"))
    )
    (net (code "30") (name "MAIN6") (class "Default")
      (node (ref "J6") (pin "15") (pinfunction "1_15") (pintype "passive"))
      (node (ref "J7") (pin "18") (pinfunction "1_18") (pintype "passive"))
    )
    (net (code "31") (name "MAIN7") (class "Default")
      (node (ref "J6") (pin "12") (pinfunction "1_12") (pintype "passive"))
      (node (ref "J7") (pin "21") (pinfunction "1_21") (pintype "passive"))
    )
    (net (code "32") (name "MAIN8") (class "Default")
      (node (ref "J6") (pin "9") (pinfunction "1_9") (pintype "passive"))
      (node (ref "J7") (pin "24") (pinfunction "1_24") (pintype "passive"))
    )
    (net (code "33") (name "Net-(F11-1)") (class "Default")
      (node (ref "F11") (pin "P$1") (pinfunction "1_P$1") (pintype "passive"))
      (node (ref "J11") (pin "1") (pinfunction "1_1") (pintype "passive"))
    )
    (net (code "34") (name "Net-(F12-Pad1)") (class "Default")
      (node (ref "F12") (pin "1") (pinfunction "1_1") (pintype "passive"))
      (node (ref "J12") (pin "1") (pinfunction "1_1") (pintype "passive"))
    )
    (net (code "35") (name "Net-(F14-Pad1)") (class "Default")
      (node (ref "F14") (pin "1") (pinfunction "1_1") (pintype "passive"))
      (node (ref "J14") (pin "1") (pinfunction "1_1") (pintype "passive"))
    )
    (net (code "36") (name "Net-(F15-Pad1)") (class "Default")
      (node (ref "F15") (pin "1") (pinfunction "1_1") (pintype "passive"))
      (node (ref "J10") (pin "1") (pinfunction "1_1") (pintype "passive"))
    )
    (net (code "37") (name "Net-(F16-1)") (class "Default")
      (node (ref "F16") (pin "P$1") (pinfunction "1_P$1") (pintype "passive"))
      (node (ref "JP1") (pin "2") (pinfunction "2_2") (pintype "passive"))
      (node (ref "U11") (pin "LH1") (pinfunction "LOAD_HIGH1_LH1") (pintype "bidirectional"))
      (node (ref "U11") (pin "LH2") (pinfunction "LOAD_HIGH2_LH2") (pintype "bidirectional"))
      (node (ref "U11") (pin "LH3") (pinfunction "LOAD_HIGH3_LH3") (pintype "bidirectional"))
      (node (ref "U11") (pin "LH4") (pinfunction "LOAD_HIGH4_LH4") (pintype "bidirectional"))
    )
    (net (code "38") (name "Net-(F16-2)") (class "Default")
      (node (ref "F16") (pin "P$2") (pinfunction "2_P$2") (pintype "passive"))
      (node (ref "J15") (pin "1") (pinfunction "1_1") (pintype "passive"))
    )
    (net (code "39") (name "Net-(F18-2)") (class "Default")
      (node (ref "F18") (pin "P$2") (pinfunction "2_P$2") (pintype "passive"))
      (node (ref "J17") (pin "1") (pinfunction "1_1") (pintype "passive"))
    )
    (net (code "40") (name "Net-(F19-2)") (class "Default")
      (node (ref "F19") (pin "P$2") (pinfunction "2_P$2") (pintype "passive"))
      (node (ref "J18") (pin "1") (pinfunction "1_1") (pintype "passive"))
    )
    (net (code "41") (name "Net-(F20-1)") (class "Default")
      (node (ref "F20") (pin "P$1") (pinfunction "1_P$1") (pintype "passive"))
      (node (ref "J19") (pin "1") (pinfunction "1_1") (pintype "passive"))
    )
    (net (code "42") (name "Net-(F21-2)") (class "Default")
      (node (ref "F21") (pin "P$2") (pinfunction "2_P$2") (pintype "passive"))
      (node (ref "J19") (pin "2") (pinfunction "2_2") (pintype "passive"))
    )
    (net (code "43") (name "Net-(F22-1)") (class "Default")
      (node (ref "F22") (pin "P$1") (pinfunction "1_P$1") (pintype "passive"))
      (node (ref "J20") (pin "1") (pinfunction "1_1") (pintype "passive"))
    )
    (net (code "44") (name "Net-(F23-2)") (class "Default")
      (node (ref "F23") (pin "P$2") (pinfunction "2_P$2") (pintype "passive"))
      (node (ref "J20") (pin "2") (pinfunction "2_2") (pintype "passive"))
    )
    (net (code "45") (name "Net-(F24-1)") (class "Default")
      (node (ref "F24") (pin "P$1") (pinfunction "1_P$1") (pintype "passive"))
      (node (ref "J21") (pin "1") (pinfunction "1_1") (pintype "passive"))
    )
    (net (code "46") (name "Net-(F25-1)") (class "Default")
      (node (ref "F25") (pin "P$1") (pinfunction "1_P$1") (pintype "passive"))
      (node (ref "J21") (pin "2") (pinfunction "2_2") (pintype "passive"))
    )
    (net (code "47") (name "Net-(F26-1)") (class "Default")
      (node (ref "F26") (pin "P$1") (pinfunction "1_P$1") (pintype "passive"))
      (node (ref "J22") (pin "1") (pinfunction "1_1") (pintype "passive"))
    )
    (net (code "48") (name "Net-(F27-1)") (class "Default")
      (node (ref "F27") (pin "P$1") (pinfunction "1_P$1") (pintype "passive"))
      (node (ref "J22") (pin "2") (pinfunction "2_2") (pintype "passive"))
    )
    (net (code "49") (name "Net-(F28-Pad1)") (class "Default")
      (node (ref "F28") (pin "1") (pinfunction "1_1") (pintype "passive"))
      (node (ref "J3") (pin "P1") (pinfunction "P1_P1") (pintype "bidirectional"))
      (node (ref "J3") (pin "P2") (pinfunction "P2_P2") (pintype "bidirectional"))
    )
    (net (code "50") (name "Net-(H1-MOUNT)") (class "Default")
      (node (ref "H1") (pin "B3,2") (pinfunction "MOUNT_B3,2") (pintype "passive"))
      (node (ref "R18") (pin "2") (pinfunction "2_2") (pintype "passive"))
    )
    (net (code "51") (name "Net-(J1-P$1)") (class "Default")
      (node (ref "J1") (pin "1") (pinfunction "P$1_1") (pintype "bidirectional"))
      (node (ref "J1") (pin "2") (pinfunction "P$2_2") (pintype "bidirectional"))
      (node (ref "R5") (pin "I2") (pinfunction "I2_I2") (pintype "bidirectional"))
      (node (ref "R7") (pin "2") (pinfunction "2_2") (pintype "passive"))
      (node (ref "U6") (pin "5") (pinfunction "V+_5") (pintype "bidirectional"))
    )
    (net (code "52") (name "Net-(J6AC-1)") (class "Default")
      (node (ref "F10") (pin "1") (pinfunction "1_1") (pintype "passive"))
      (node (ref "J6") (pin "11") (pinfunction "1_11") (pintype "passive"))
      (node (ref "J6") (pin "14") (pinfunction "1_14") (pintype "passive"))
      (node (ref "J6") (pin "17") (pinfunction "1_17") (pintype "passive"))
      (node (ref "J6") (pin "2") (pinfunction "1_2") (pintype "passive"))
      (node (ref "J6") (pin "20") (pinfunction "1_20") (pintype "passive"))
      (node (ref "J6") (pin "23") (pinfunction "1_23") (pintype "passive"))
      (node (ref "J6") (pin "26") (pinfunction "1_26") (pintype "passive"))
      (node (ref "J6") (pin "29") (pinfunction "1_29") (pintype "passive"))
      (node (ref "J6") (pin "32") (pinfunction "1_32") (pintype "passive"))
      (node (ref "J6") (pin "35") (pinfunction "1_35") (pintype "passive"))
      (node (ref "J6") (pin "38") (pinfunction "1_38") (pintype "passive"))
      (node (ref "J6") (pin "41") (pinfunction "1_41") (pintype "passive"))
      (node (ref "J6") (pin "44") (pinfunction "1_44") (pintype "passive"))
      (node (ref "J6") (pin "47") (pinfunction "1_47") (pintype "passive"))
      (node (ref "J6") (pin "5") (pinfunction "1_5") (pintype "passive"))
      (node (ref "J6") (pin "8") (pinfunction "1_8") (pintype "passive"))
    )
    (net (code "53") (name "Net-(J8K-1)") (class "Default")
      (node (ref "J8") (pin "4") (pinfunction "1_4") (pintype "passive"))
      (node (ref "J8") (pin "6") (pinfunction "1_6") (pintype "passive"))
    )
    (net (code "54") (name "Net-(J9F-1)") (class "Default")
      (node (ref "F29") (pin "1") (pinfunction "1_1") (pintype "passive"))
      (node (ref "J9") (pin "3") (pinfunction "1_3") (pintype "passive"))
    )
    (net (code "55") (name "Net-(LED1-PadC)") (class "Default")
      (node (ref "LED1") (pin "C") (pinfunction "C_C") (pintype "passive"))
      (node (ref "R13") (pin "2") (pinfunction "2_2") (pintype "passive"))
    )
    (net (code "56") (name "Net-(LED2-PadC)") (class "Default")
      (node (ref "LED2") (pin "C") (pinfunction "C_C") (pintype "passive"))
      (node (ref "R14") (pin "2") (pinfunction "2_2") (pintype "passive"))
    )
    (net (code "57") (name "Net-(R16-Pad2)") (class "Default")
      (node (ref "R16") (pin "2") (pinfunction "2_2") (pintype "passive"))
      (node (ref "SW1") (pin "GND1") (pinfunction "GND1_GND1") (pintype "bidirectional"))
      (node (ref "SW1") (pin "GND2") (pinfunction "GND2_GND2") (pintype "bidirectional"))
      (node (ref "SW1") (pin "GND3") (pinfunction "GND3_GND3") (pintype "bidirectional"))
      (node (ref "SW1") (pin "GND4") (pinfunction "GND4_GND4") (pintype "bidirectional"))
    )
    (net (code "58") (name "Net-(R17-Pad2)") (class "Default")
      (node (ref "R17") (pin "2") (pinfunction "2_2") (pintype "passive"))
      (node (ref "SW2") (pin "GND1") (pinfunction "GND1_GND1") (pintype "bidirectional"))
      (node (ref "SW2") (pin "GND2") (pinfunction "GND2_GND2") (pintype "bidirectional"))
      (node (ref "SW2") (pin "GND3") (pinfunction "GND3_GND3") (pintype "bidirectional"))
      (node (ref "SW2") (pin "GND4") (pinfunction "GND4_GND4") (pintype "bidirectional"))
    )
    (net (code "59") (name "Net-(U1-CASE)") (class "Default")
      (node (ref "C3") (pin "2") (pinfunction "2_2") (pintype "passive"))
      (node (ref "U1") (pin "P3") (pinfunction "CASE_P3") (pintype "bidirectional"))
    )
    (net (code "60") (name "Net-(U1-SENSE+)") (class "Default")
      (node (ref "R3") (pin "1") (pinfunction "1_1") (pintype "passive"))
      (node (ref "R9") (pin "I2") (pinfunction "I2_I2") (pintype "bidirectional"))
      (node (ref "U1") (pin "P8") (pinfunction "SENSE+_P8") (pintype "bidirectional"))
      (node (ref "U1") (pin "P9") (pinfunction "VOUT+_P9") (pintype "bidirectional"))
      (node (ref "U4") (pin "5") (pinfunction "V+_5") (pintype "bidirectional"))
    )
    (net (code "61") (name "Net-(U1-TRIM)") (class "Default")
      (node (ref "R3") (pin "2") (pinfunction "2_2") (pintype "passive"))
      (node (ref "R4") (pin "1") (pinfunction "1_1") (pintype "passive"))
      (node (ref "U1") (pin "P7") (pinfunction "TRIM_P7") (pintype "bidirectional"))
    )
    (net (code "62") (name "Net-(U2-CASE)") (class "Default")
      (node (ref "C4") (pin "2") (pinfunction "2_2") (pintype "passive"))
      (node (ref "U2") (pin "P3") (pinfunction "CASE_P3") (pintype "bidirectional"))
    )
    (net (code "63") (name "Net-(U2-SENSE+)") (class "Default")
      (node (ref "R1") (pin "1") (pinfunction "1_1") (pintype "passive"))
      (node (ref "R11") (pin "I2") (pinfunction "I2_I2") (pintype "bidirectional"))
      (node (ref "U2") (pin "P8") (pinfunction "SENSE+_P8") (pintype "bidirectional"))
      (node (ref "U2") (pin "P9") (pinfunction "VOUT+_P9") (pintype "bidirectional"))
      (node (ref "U5") (pin "5") (pinfunction "V+_5") (pintype "bidirectional"))
    )
    (net (code "64") (name "Net-(U2-TRIM)") (class "Default")
      (node (ref "R1") (pin "2") (pinfunction "2_2") (pintype "passive"))
      (node (ref "R2") (pin "1") (pinfunction "1_1") (pintype "passive"))
      (node (ref "U2") (pin "P7") (pinfunction "TRIM_P7") (pintype "bidirectional"))
    )
    (net (code "65") (name "Net-(U4-VIN+)") (class "Default")
      (node (ref "R9") (pin "V1") (pinfunction "V1_V1") (pintype "bidirectional"))
      (node (ref "U4") (pin "4") (pinfunction "VIN+_4") (pintype "bidirectional"))
    )
    (net (code "66") (name "Net-(U4-VIN-)") (class "Default")
      (node (ref "R9") (pin "V2") (pinfunction "V2_V2") (pintype "bidirectional"))
      (node (ref "U4") (pin "3") (pinfunction "VIN-_3") (pintype "bidirectional"))
    )
    (net (code "67") (name "Net-(U5-VIN+)") (class "Default")
      (node (ref "R11") (pin "V1") (pinfunction "V1_V1") (pintype "bidirectional"))
      (node (ref "U5") (pin "4") (pinfunction "VIN+_4") (pintype "bidirectional"))
    )
    (net (code "68") (name "Net-(U5-VIN-)") (class "Default")
      (node (ref "R11") (pin "V2") (pinfunction "V2_V2") (pintype "bidirectional"))
      (node (ref "U5") (pin "3") (pinfunction "VIN-_3") (pintype "bidirectional"))
    )
    (net (code "69") (name "Net-(U6-VIN+)") (class "Default")
      (node (ref "R5") (pin "V1") (pinfunction "V1_V1") (pintype "bidirectional"))
      (node (ref "U6") (pin "4") (pinfunction "VIN+_4") (pintype "bidirectional"))
    )
    (net (code "70") (name "Net-(U6-VIN-)") (class "Default")
      (node (ref "R5") (pin "V2") (pinfunction "V2_V2") (pintype "bidirectional"))
      (node (ref "U6") (pin "3") (pinfunction "VIN-_3") (pintype "bidirectional"))
    )
    (net (code "71") (name "Net-(U11-LOAD_LOW1)") (class "Default")
      (node (ref "J15") (pin "2") (pinfunction "2_2") (pintype "passive"))
      (node (ref "U11") (pin "LGND") (pinfunction "LOAD_LOW1_LGND") (pintype "bidirectional"))
      (node (ref "U11") (pin "LGND2") (pinfunction "LOAD_LOW2_LGND2") (pintype "bidirectional"))
    )
    (net (code "72") (name "RCTS") (class "Default")
      (node (ref "J5") (pin "P4") (pinfunction "P4_P4") (pintype "bidirectional"))
      (node (ref "J8") (pin "3") (pinfunction "1_3") (pintype "passive"))
    )
    (net (code "73") (name "RC_SIG") (class "Default")
      (node (ref "J6") (pin "3") (pinfunction "1_3") (pintype "passive"))
      (node (ref "J9") (pin "1") (pinfunction "1_1") (pintype "passive"))
    )
    (net (code "74") (name "RRTS") (class "Default")
      (node (ref "J5") (pin "P5") (pinfunction "P5_P5") (pintype "bidirectional"))
      (node (ref "J8") (pin "11") (pinfunction "1_11") (pintype "passive"))
    )
    (net (code "75") (name "RRX") (class "Default")
      (node (ref "J5") (pin "P2") (pinfunction "P2_P2") (pintype "bidirectional"))
      (node (ref "J8") (pin "7") (pinfunction "1_7") (pintype "passive"))
    )
    (net (code "76") (name "RTX") (class "Default")
      (node (ref "J5") (pin "P3") (pinfunction "P3_P3") (pintype "bidirectional"))
      (node (ref "J8") (pin "9") (pinfunction "1_9") (pintype "passive"))
    )
    (net (code "77") (name "SBUS") (class "Default")
      (node (ref "J6") (pin "6") (pinfunction "1_6") (pintype "passive"))
    )
    (net (code "78") (name "SYNC") (class "Default")
      (node (ref "J17") (pin "3") (pinfunction "3_3") (pintype "passive"))
      (node (ref "J18") (pin "3") (pinfunction "3_3") (pintype "passive"))
      (node (ref "J19") (pin "4") (pinfunction "4_4") (pintype "passive"))
      (node (ref "J20") (pin "4") (pinfunction "4_4") (pintype "passive"))
    )
    (net (code "79") (name "V+") (class "Default")
      (node (ref "C1") (pin "1") (pinfunction "1_1") (pintype "passive"))
      (node (ref "C2") (pin "1") (pinfunction "1_1") (pintype "passive"))
      (node (ref "R5") (pin "I1") (pinfunction "I1_I1") (pintype "bidirectional"))
      (node (ref "U1") (pin "P1") (pinfunction "VIN+_P1") (pintype "bidirectional"))
      (node (ref "U2") (pin "P1") (pinfunction "VIN+_P1") (pintype "bidirectional"))
    )
    (net (code "80") (name "V-") (class "Default")
      (node (ref "C1") (pin "2") (pinfunction "2_2") (pintype "passive"))
      (node (ref "C2") (pin "2") (pinfunction "2_2") (pintype "passive"))
      (node (ref "C3") (pin "1") (pinfunction "1_1") (pintype "passive"))
      (node (ref "C4") (pin "1") (pinfunction "1_1") (pintype "passive"))
      (node (ref "J1") (pin "3") (pinfunction "P$3_3") (pintype "bidirectional"))
      (node (ref "J1") (pin "4") (pinfunction "P$4_4") (pintype "bidirectional"))
      (node (ref "U1") (pin "P4") (pinfunction "VIN-_P4") (pintype "bidirectional"))
      (node (ref "U2") (pin "P4") (pinfunction "VIN-_P4") (pintype "bidirectional"))
    )
    (net (code "81") (name "VCC_POS") (class "Default")
      (node (ref "F20") (pin "P$2") (pinfunction "2_P$2") (pintype "passive"))
      (node (ref "F22") (pin "P$2") (pinfunction "2_P$2") (pintype "passive"))
      (node (ref "U7") (pin "COM") (pinfunction "COM_COM") (pintype "bidirectional"))
    )
    (net (code "82") (name "VCC_STROBE") (class "Default")
      (node (ref "F18") (pin "P$1") (pinfunction "1_P$1") (pintype "passive"))
      (node (ref "F19") (pin "P$1") (pinfunction "1_P$1") (pintype "passive"))
      (node (ref "F21") (pin "P$1") (pinfunction "1_P$1") (pintype "passive"))
      (node (ref "F23") (pin "P$1") (pinfunction "1_P$1") (pintype "passive"))
      (node (ref "U8") (pin "COM") (pinfunction "COM_COM") (pintype "bidirectional"))
    )
    (net (code "83") (name "VCC_TAXI") (class "Default")
      (node (ref "F24") (pin "P$2") (pinfunction "2_P$2") (pintype "passive"))
      (node (ref "F25") (pin "P$2") (pinfunction "2_P$2") (pintype "passive"))
      (node (ref "F26") (pin "P$2") (pinfunction "2_P$2") (pintype "passive"))
      (node (ref "F27") (pin "P$2") (pinfunction "2_P$2") (pintype "passive"))
      (node (ref "U9") (pin "COM") (pinfunction "COM_COM") (pintype "bidirectional"))
    )
    (net (code "84") (name "V_MEAS") (class "Default")
      (node (ref "C5") (pin "1") (pinfunction "1_1") (pintype "passive"))
      (node (ref "J3") (pin "P4") (pinfunction "P4_P4") (pintype "bidirectional"))
      (node (ref "R7") (pin "1") (pinfunction "1_1") (pintype "passive"))
      (node (ref "R8") (pin "2") (pinfunction "2_2") (pintype "passive"))
    )
    (net (code "85") (name "unconnected-(J4-PadP1)") (class "Default")
      (node (ref "J4") (pin "P1") (pinfunction "P1_P1") (pintype "bidirectional"))
    )
    (net (code "86") (name "unconnected-(J5-PadP1)") (class "Default")
      (node (ref "J5") (pin "P1") (pinfunction "P1_P1") (pintype "bidirectional"))
    )
    (net (code "87") (name "unconnected-(J8B-1-Pad10)") (class "Default")
      (node (ref "J8") (pin "10") (pinfunction "1_10") (pintype "passive"))
    )
    (net (code "88") (name "unconnected-(J8D-1-Pad12)") (class "Default")
      (node (ref "J8") (pin "12") (pinfunction "1_12") (pintype "passive"))
    )
    (net (code "89") (name "unconnected-(J8E-1-Pad13)") (class "Default")
      (node (ref "J8") (pin "13") (pinfunction "1_13") (pintype "passive"))
    )
    (net (code "90") (name "unconnected-(J8F-1-Pad14)") (class "Default")
      (node (ref "J8") (pin "14") (pinfunction "1_14") (pintype "passive"))
    )
    (net (code "91") (name "unconnected-(J8G-1-Pad15)") (class "Default")
      (node (ref "J8") (pin "15") (pinfunction "1_15") (pintype "passive"))
    )
    (net (code "92") (name "unconnected-(J8H-1-Pad16)") (class "Default")
      (node (ref "J8") (pin "16") (pinfunction "1_16") (pintype "passive"))
    )
    (net (code "93") (name "unconnected-(J8I-1-Pad2)") (class "Default")
      (node (ref "J8") (pin "2") (pinfunction "1_2") (pintype "passive"))
    )
    (net (code "94") (name "unconnected-(J8O-1-Pad8)") (class "Default")
      (node (ref "J8") (pin "8") (pinfunction "1_8") (pintype "passive"))
    )
    (net (code "95") (name "unconnected-(J9B-1-Pad10)") (class "Default")
      (node (ref "J9") (pin "10") (pinfunction "1_10") (pintype "passive"))
    )
    (net (code "96") (name "unconnected-(J9C-1-Pad11)") (class "Default")
      (node (ref "J9") (pin "11") (pinfunction "1_11") (pintype "passive"))
    )
    (net (code "97") (name "unconnected-(J9D-1-Pad12)") (class "Default")
      (node (ref "J9") (pin "12") (pinfunction "1_12") (pintype "passive"))
    )
    (net (code "98") (name "unconnected-(J9E-1-Pad2)") (class "Default")
      (node (ref "J9") (pin "2") (pinfunction "1_2") (pintype "passive"))
    )
    (net (code "99") (name "unconnected-(J9G-1-Pad4)") (class "Default")
      (node (ref "J9") (pin "4") (pinfunction "1_4") (pintype "passive"))
    )
    (net (code "100") (name "unconnected-(J9I-1-Pad6)") (class "Default")
      (node (ref "J9") (pin "6") (pinfunction "1_6") (pintype "passive"))
    )
    (net (code "101") (name "unconnected-(J9J-1-Pad7)") (class "Default")
      (node (ref "J9") (pin "7") (pinfunction "1_7") (pintype "passive"))
    )
    (net (code "102") (name "unconnected-(J9K-1-Pad8)") (class "Default")
      (node (ref "J9") (pin "8") (pinfunction "1_8") (pintype "passive"))
    )
    (net (code "103") (name "unconnected-(J9L-1-Pad9)") (class "Default")
      (node (ref "J9") (pin "9") (pinfunction "1_9") (pintype "passive"))
    )
    (net (code "104") (name "unconnected-(SW1-NC-PadP3)") (class "Default")
      (node (ref "SW1") (pin "P3") (pinfunction "NC_P3") (pintype "passive"))
    )
    (net (code "105") (name "unconnected-(SW1-NC1-PadP6)") (class "Default")
      (node (ref "SW1") (pin "P6") (pinfunction "NC1_P6") (pintype "passive"))
    )
    (net (code "106") (name "unconnected-(SW2-NC-PadP3)") (class "Default")
      (node (ref "SW2") (pin "P3") (pinfunction "NC_P3") (pintype "passive"))
    )
    (net (code "107") (name "unconnected-(SW2-NC1-PadP6)") (class "Default")
      (node (ref "SW2") (pin "P6") (pinfunction "NC1_P6") (pintype "passive"))
    )
    (net (code "108") (name "unconnected-(U7-PadNC)") (class "Default")
      (node (ref "U7") (pin "NC") (pinfunction "NC_NC") (pintype "bidirectional"))
    )
    (net (code "109") (name "unconnected-(U8-PadNC)") (class "Default")
      (node (ref "U8") (pin "NC") (pinfunction "NC_NC") (pintype "bidirectional"))
    )
    (net (code "110") (name "unconnected-(U9-PadNC)") (class "Default")
      (node (ref "U9") (pin "NC") (pinfunction "NC_NC") (pintype "bidirectional"))
    )
  )
)
